# Buck_3V3.net
KiCad netlist of a schematic drawn in Altium Designer
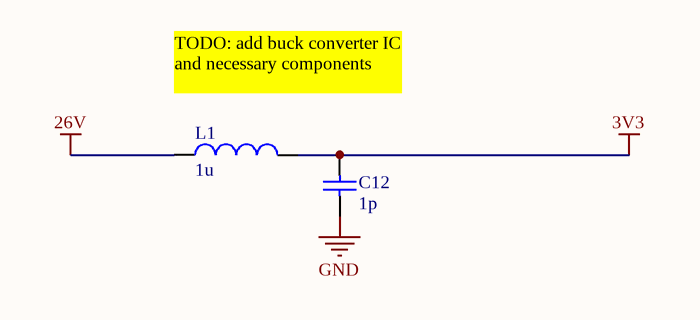
[diagram p0: Buck 3V3.SchDoc]

(export (version "E")
  (design (tool "Eeschema 10.0.6"))
  (components
    (comp (ref "C12")
      (value "1p")
      (description "Capacitor")
      (libsource (lib "Simulation Generic Components") (part "Capacitor"))
    )
    (comp (ref "L1")
      (value "1u")
      (description "Inductor")
      (libsource (lib "Simulation Generic Components") (part "Inductor"))
    )
  )
  (nets
    (net (code "1") (name "3V3") (class "Default")
      (node (ref "C12") (pin "2") (pinfunction "2_2") (pintype "passive"))
      (node (ref "L1") (pin "2") (pinfunction "2_2") (pintype "passive"))
    )
    (net (code "2") (name "26V") (class "Default")
      (node (ref "L1") (pin "1") (pinfunction "1_1") (pintype "passive"))
    )
    (net (code "3") (name "GND") (class "Default")
      (node (ref "C12") (pin "1") (pinfunction "1_1") (pintype "passive"))
    )
  )
)
